# memoryboard31.net
KiCad netlist of a schematic drawn in EAGLE
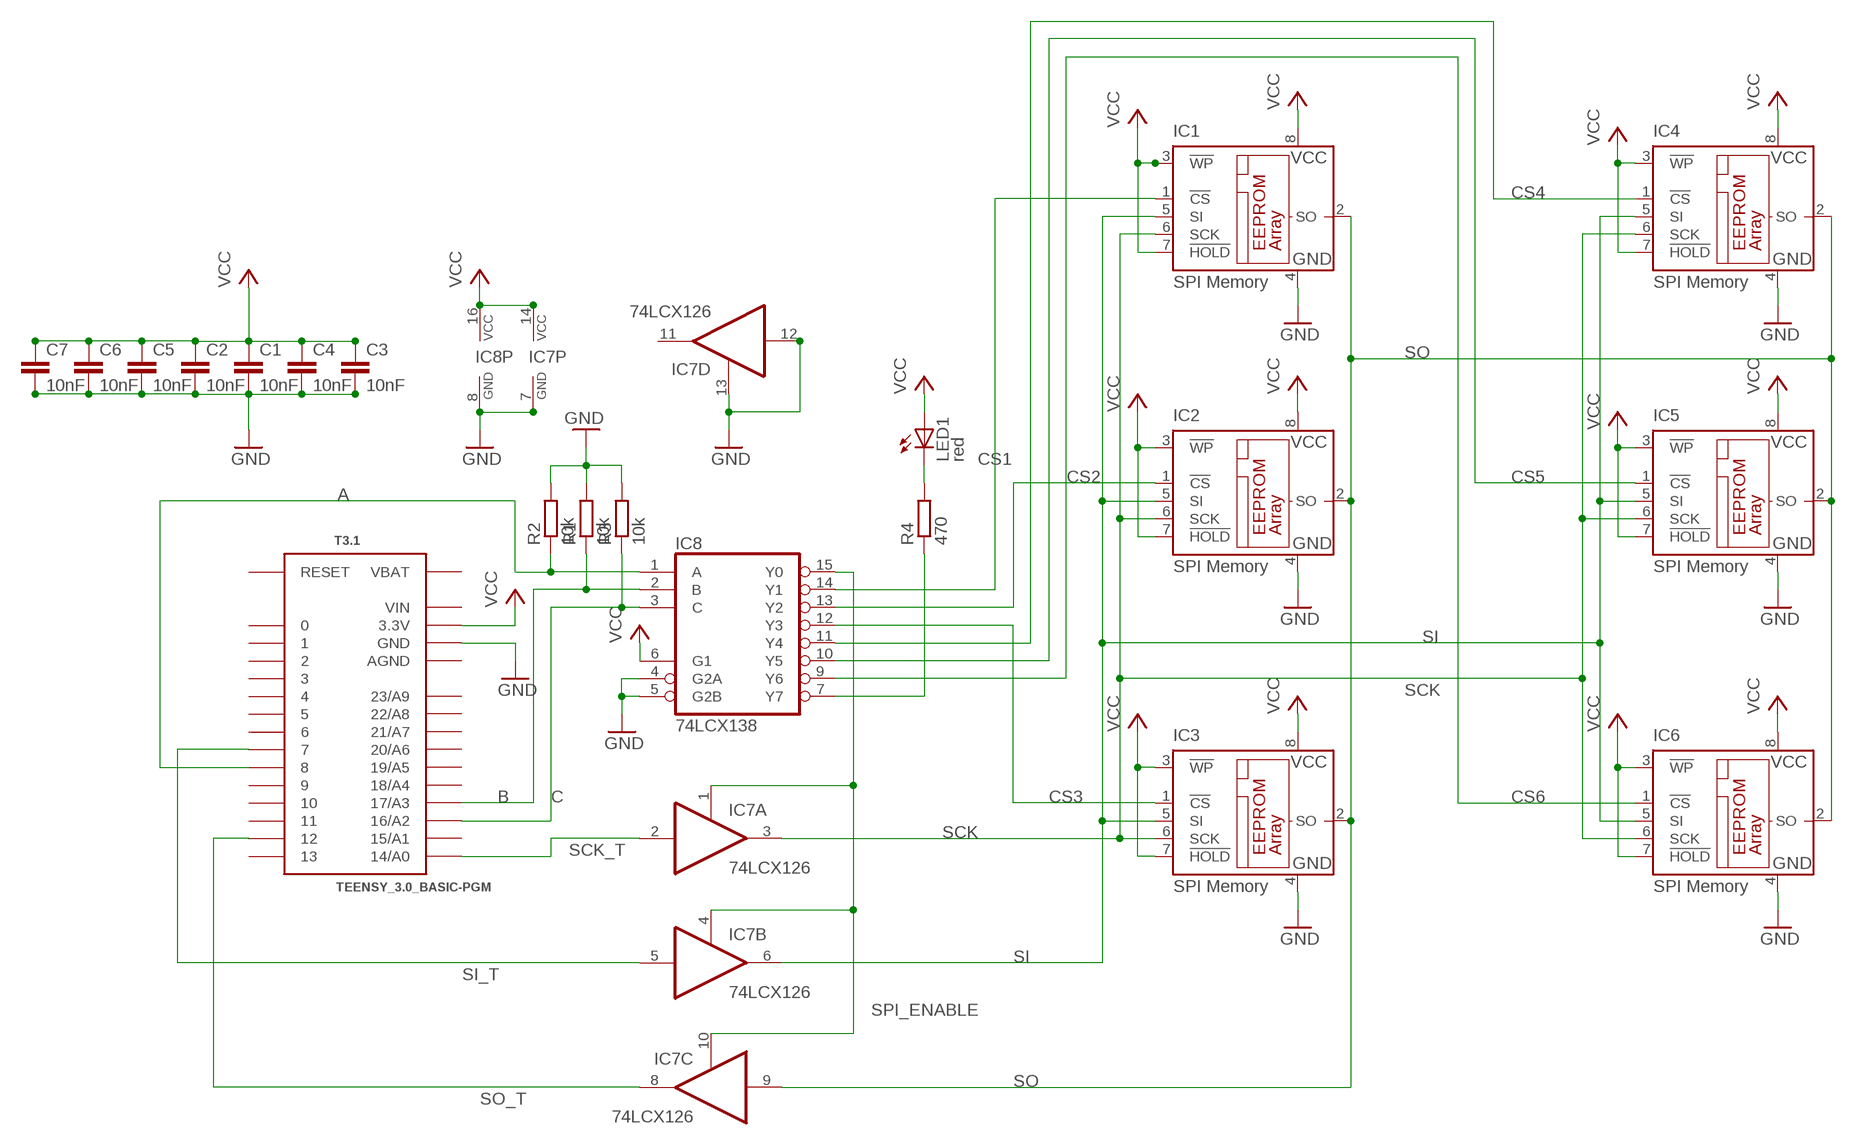
[diagram p0: schematic, sheet 1]

(export (version "E")
  (design (tool "Eeschema 10.0.6"))
  (components
    (comp (ref "C1")
      (value "10nF")
      (footprint "eagle-import:C0603")
      (libsource (lib "eagle-import") (part "C-EUC0603"))
    )
    (comp (ref "C2")
      (value "10nF")
      (footprint "eagle-import:C0603")
      (libsource (lib "eagle-import") (part "C-EUC0603"))
    )
    (comp (ref "C3")
      (value "10nF")
      (footprint "eagle-import:C0603")
      (libsource (lib "eagle-import") (part "C-EUC0603"))
    )
    (comp (ref "C4")
      (value "10nF")
      (footprint "eagle-import:C0603")
      (libsource (lib "eagle-import") (part "C-EUC0603"))
    )
    (comp (ref "C5")
      (value "10nF")
      (footprint "eagle-import:C0603")
      (libsource (lib "eagle-import") (part "C-EUC0603"))
    )
    (comp (ref "C6")
      (value "10nF")
      (footprint "eagle-import:C0603")
      (libsource (lib "eagle-import") (part "C-EUC0603"))
    )
    (comp (ref "C7")
      (value "10nF")
      (footprint "eagle-import:C0603")
      (libsource (lib "eagle-import") (part "C-EUC0603"))
    )
    (comp (ref "IC1")
      (value "SPI Memory")
      (footprint "eagle-import:SO-08")
      (fields (field (name "MF") "MICROCHIP") (field (name "MPN") "25C080/SN"))
      (libsource (lib "eagle-import") (part "25SNC080"))
    )
    (comp (ref "IC2")
      (value "SPI Memory")
      (footprint "eagle-import:SO-08")
      (fields (field (name "MF") "MICROCHIP") (field (name "MPN") "25C080/SN"))
      (libsource (lib "eagle-import") (part "25SNC080"))
    )
    (comp (ref "IC3")
      (value "SPI Memory")
      (footprint "eagle-import:SO-08")
      (fields (field (name "MF") "MICROCHIP") (field (name "MPN") "25C080/SN"))
      (libsource (lib "eagle-import") (part "25SNC080"))
    )
    (comp (ref "IC4")
      (value "SPI Memory")
      (footprint "eagle-import:SO-08")
      (fields (field (name "MF") "MICROCHIP") (field (name "MPN") "25C080/SN"))
      (libsource (lib "eagle-import") (part "25SNC080"))
    )
    (comp (ref "IC5")
      (value "SPI Memory")
      (footprint "eagle-import:SO-08")
      (fields (field (name "MF") "MICROCHIP") (field (name "MPN") "25C080/SN"))
      (libsource (lib "eagle-import") (part "25SNC080"))
    )
    (comp (ref "IC6")
      (value "SPI Memory")
      (footprint "eagle-import:SO-08")
      (fields (field (name "MF") "MICROCHIP") (field (name "MPN") "25C080/SN"))
      (libsource (lib "eagle-import") (part "25SNC080"))
    )
    (comp (ref "IC7")
      (value "74LCX126")
      (footprint "eagle-import:SO14")
      (libsource (lib "eagle-import") (part "74126DAC"))
    )
    (comp (ref "IC8")
      (value "74LCX138")
      (footprint "eagle-import:SO16")
      (libsource (lib "eagle-import") (part "74138DHC"))
    )
    (comp (ref "LED1")
      (value "red")
      (footprint "eagle-import:SML0603")
      (libsource (lib "eagle-import") (part "LEDSML0603"))
    )
    (comp (ref "R1")
      (value "10k")
      (footprint "eagle-import:R0603")
      (libsource (lib "eagle-import") (part "R-EU_R0603"))
    )
    (comp (ref "R2")
      (value "10k")
      (footprint "eagle-import:R0603")
      (libsource (lib "eagle-import") (part "R-EU_R0603"))
    )
    (comp (ref "R3")
      (value "10k")
      (footprint "eagle-import:R0603")
      (libsource (lib "eagle-import") (part "R-EU_R0603"))
    )
    (comp (ref "R4")
      (value "470")
      (footprint "eagle-import:R0603")
      (libsource (lib "eagle-import") (part "R-EU_R0603"))
    )
    (comp (ref "T3.1")
      (value "TEENSY_3.0_BASIC-PGM")
      (footprint "eagle-import:TEENSY_3.0_BASIC-PGM")
      (libsource (lib "eagle-import") (part "TEENSY_3.0_BASIC-PGM"))
    )
  )
  (nets
    (net (code "1") (name "/A") (class "Default")
      (node (ref "IC8") (pin "1") (pinfunction "A_1") (pintype "input"))
      (node (ref "R2") (pin "1") (pinfunction "1_1") (pintype "passive"))
      (node (ref "T3.1") (pin "8") (pinfunction "8_8") (pintype "bidirectional"))
    )
    (net (code "2") (name "/AGND") (class "Default")
      (node (ref "T3.1") (pin "AGND") (pinfunction "AGND_AGND") (pintype "power_in"))
    )
    (net (code "3") (name "/B") (class "Default")
      (node (ref "IC8") (pin "2") (pinfunction "B_2") (pintype "input"))
      (node (ref "R1") (pin "1") (pinfunction "1_1") (pintype "passive"))
      (node (ref "T3.1") (pin "17/A3") (pinfunction "17/A3_17/A3") (pintype "bidirectional"))
    )
    (net (code "4") (name "/C") (class "Default")
      (node (ref "IC8") (pin "3") (pinfunction "C_3") (pintype "input"))
      (node (ref "R3") (pin "1") (pinfunction "1_1") (pintype "passive"))
      (node (ref "T3.1") (pin "16/A2") (pinfunction "16/A2_16/A2") (pintype "bidirectional"))
    )
    (net (code "5") (name "/CS1") (class "Default")
      (node (ref "IC1") (pin "1") (pinfunction "~{CS}_1") (pintype "input"))
      (node (ref "IC8") (pin "14") (pinfunction "Y1_14") (pintype "output"))
    )
    (net (code "6") (name "/CS2") (class "Default")
      (node (ref "IC2") (pin "1") (pinfunction "~{CS}_1") (pintype "input"))
      (node (ref "IC8") (pin "13") (pinfunction "Y2_13") (pintype "output"))
    )
    (net (code "7") (name "/CS3") (class "Default")
      (node (ref "IC3") (pin "1") (pinfunction "~{CS}_1") (pintype "input"))
      (node (ref "IC8") (pin "12") (pinfunction "Y3_12") (pintype "output"))
    )
    (net (code "8") (name "/CS4") (class "Default")
      (node (ref "IC4") (pin "1") (pinfunction "~{CS}_1") (pintype "input"))
      (node (ref "IC8") (pin "11") (pinfunction "Y4_11") (pintype "output"))
    )
    (net (code "9") (name "/CS5") (class "Default")
      (node (ref "IC5") (pin "1") (pinfunction "~{CS}_1") (pintype "input"))
      (node (ref "IC8") (pin "10") (pinfunction "Y5_10") (pintype "output"))
    )
    (net (code "10") (name "/CS6") (class "Default")
      (node (ref "IC6") (pin "1") (pinfunction "~{CS}_1") (pintype "input"))
      (node (ref "IC8") (pin "9") (pinfunction "Y6_9") (pintype "output"))
    )
    (net (code "11") (name "/SCK") (class "Default")
      (node (ref "IC1") (pin "6") (pinfunction "SCK_6") (pintype "input"))
      (node (ref "IC2") (pin "6") (pinfunction "SCK_6") (pintype "input"))
      (node (ref "IC3") (pin "6") (pinfunction "SCK_6") (pintype "input"))
      (node (ref "IC4") (pin "6") (pinfunction "SCK_6") (pintype "input"))
      (node (ref "IC5") (pin "6") (pinfunction "SCK_6") (pintype "input"))
      (node (ref "IC6") (pin "6") (pinfunction "SCK_6") (pintype "input"))
      (node (ref "IC7") (pin "3") (pinfunction "O_3") (pintype "output"))
    )
    (net (code "12") (name "/SCK_T") (class "Default")
      (node (ref "IC7") (pin "2") (pinfunction "I_2") (pintype "input"))
      (node (ref "T3.1") (pin "14/A0") (pinfunction "14/A0_14/A0") (pintype "bidirectional"))
    )
    (net (code "13") (name "/SI") (class "Default")
      (node (ref "IC1") (pin "5") (pinfunction "SI_5") (pintype "input"))
      (node (ref "IC2") (pin "5") (pinfunction "SI_5") (pintype "input"))
      (node (ref "IC3") (pin "5") (pinfunction "SI_5") (pintype "input"))
      (node (ref "IC4") (pin "5") (pinfunction "SI_5") (pintype "input"))
      (node (ref "IC5") (pin "5") (pinfunction "SI_5") (pintype "input"))
      (node (ref "IC6") (pin "5") (pinfunction "SI_5") (pintype "input"))
      (node (ref "IC7") (pin "6") (pinfunction "O_6") (pintype "output"))
    )
    (net (code "14") (name "/SI_T") (class "Default")
      (node (ref "IC7") (pin "5") (pinfunction "I_5") (pintype "input"))
      (node (ref "T3.1") (pin "7") (pinfunction "7_7") (pintype "bidirectional"))
    )
    (net (code "15") (name "/SO") (class "Default")
      (node (ref "IC1") (pin "2") (pinfunction "SO_2") (pintype "bidirectional"))
      (node (ref "IC2") (pin "2") (pinfunction "SO_2") (pintype "bidirectional"))
      (node (ref "IC3") (pin "2") (pinfunction "SO_2") (pintype "bidirectional"))
      (node (ref "IC4") (pin "2") (pinfunction "SO_2") (pintype "bidirectional"))
      (node (ref "IC5") (pin "2") (pinfunction "SO_2") (pintype "bidirectional"))
      (node (ref "IC6") (pin "2") (pinfunction "SO_2") (pintype "bidirectional"))
      (node (ref "IC7") (pin "9") (pinfunction "I_9") (pintype "input"))
    )
    (net (code "16") (name "/SO_T") (class "Default")
      (node (ref "IC7") (pin "8") (pinfunction "O_8") (pintype "output"))
      (node (ref "T3.1") (pin "12") (pinfunction "12_12") (pintype "bidirectional"))
    )
    (net (code "17") (name "/SPI_ENABLE") (class "Default")
      (node (ref "IC7") (pin "1") (pinfunction "OE_1") (pintype "input"))
      (node (ref "IC7") (pin "10") (pinfunction "OE_10") (pintype "input"))
      (node (ref "IC7") (pin "4") (pinfunction "OE_4") (pintype "input"))
      (node (ref "IC8") (pin "15") (pinfunction "Y0_15") (pintype "output"))
    )
    (net (code "18") (name "/VBAT") (class "Default")
      (node (ref "T3.1") (pin "VBAT") (pinfunction "VBAT_VBAT") (pintype "power_in"))
    )
    (net (code "19") (name "/VIN") (class "Default")
      (node (ref "T3.1") (pin "VIN") (pinfunction "VIN_VIN") (pintype "power_in"))
    )
    (net (code "20") (name "GND") (class "Default")
      (node (ref "C1") (pin "2") (pinfunction "2_2") (pintype "passive"))
      (node (ref "C2") (pin "2") (pinfunction "2_2") (pintype "passive"))
      (node (ref "C3") (pin "2") (pinfunction "2_2") (pintype "passive"))
      (node (ref "C4") (pin "2") (pinfunction "2_2") (pintype "passive"))
      (node (ref "C5") (pin "2") (pinfunction "2_2") (pintype "passive"))
      (node (ref "C6") (pin "2") (pinfunction "2_2") (pintype "passive"))
      (node (ref "C7") (pin "2") (pinfunction "2_2") (pintype "passive"))
      (node (ref "IC1") (pin "4") (pinfunction "GND_4") (pintype "power_in"))
      (node (ref "IC2") (pin "4") (pinfunction "GND_4") (pintype "power_in"))
      (node (ref "IC3") (pin "4") (pinfunction "GND_4") (pintype "power_in"))
      (node (ref "IC4") (pin "4") (pinfunction "GND_4") (pintype "power_in"))
      (node (ref "IC5") (pin "4") (pinfunction "GND_4") (pintype "power_in"))
      (node (ref "IC6") (pin "4") (pinfunction "GND_4") (pintype "power_in"))
      (node (ref "IC7") (pin "12") (pinfunction "I_12") (pintype "input"))
      (node (ref "IC7") (pin "13") (pinfunction "OE_13") (pintype "input"))
      (node (ref "IC7") (pin "7") (pinfunction "GND_7") (pintype "power_in"))
      (node (ref "IC8") (pin "4") (pinfunction "G2A_4") (pintype "input"))
      (node (ref "IC8") (pin "5") (pinfunction "G2B_5") (pintype "input"))
      (node (ref "IC8") (pin "8") (pinfunction "GND_8") (pintype "power_in"))
      (node (ref "R1") (pin "2") (pinfunction "2_2") (pintype "passive"))
      (node (ref "R2") (pin "2") (pinfunction "2_2") (pintype "passive"))
      (node (ref "R3") (pin "2") (pinfunction "2_2") (pintype "passive"))
      (node (ref "T3.1") (pin "GND") (pinfunction "GND_GND") (pintype "power_in"))
      (node (ref "T3.1") (pin "GND1") (pinfunction "GND_GND1") (pintype "power_in"))
    )
    (net (code "21") (name "Net-(IC8A-Y7)") (class "Default")
      (node (ref "IC8") (pin "7") (pinfunction "Y7_7") (pintype "output"))
      (node (ref "R4") (pin "1") (pinfunction "1_1") (pintype "passive"))
    )
    (net (code "22") (name "Net-(LED1-PadC)") (class "Default")
      (node (ref "LED1") (pin "C") (pinfunction "C_C") (pintype "passive"))
      (node (ref "R4") (pin "2") (pinfunction "2_2") (pintype "passive"))
    )
    (net (code "23") (name "VCC") (class "Default")
      (node (ref "C1") (pin "1") (pinfunction "1_1") (pintype "passive"))
      (node (ref "C2") (pin "1") (pinfunction "1_1") (pintype "passive"))
      (node (ref "C3") (pin "1") (pinfunction "1_1") (pintype "passive"))
      (node (ref "C4") (pin "1") (pinfunction "1_1") (pintype "passive"))
      (node (ref "C5") (pin "1") (pinfunction "1_1") (pintype "passive"))
      (node (ref "C6") (pin "1") (pinfunction "1_1") (pintype "passive"))
      (node (ref "C7") (pin "1") (pinfunction "1_1") (pintype "passive"))
      (node (ref "IC1") (pin "3") (pinfunction "~{WP}_3") (pintype "input"))
      (node (ref "IC1") (pin "7") (pinfunction "~{HOLD}_7") (pintype "input"))
      (node (ref "IC1") (pin "8") (pinfunction "VCC_8") (pintype "power_in"))
      (node (ref "IC2") (pin "3") (pinfunction "~{WP}_3") (pintype "input"))
      (node (ref "IC2") (pin "7") (pinfunction "~{HOLD}_7") (pintype "input"))
      (node (ref "IC2") (pin "8") (pinfunction "VCC_8") (pintype "power_in"))
      (node (ref "IC3") (pin "3") (pinfunction "~{WP}_3") (pintype "input"))
      (node (ref "IC3") (pin "7") (pinfunction "~{HOLD}_7") (pintype "input"))
      (node (ref "IC3") (pin "8") (pinfunction "VCC_8") (pintype "power_in"))
      (node (ref "IC4") (pin "3") (pinfunction "~{WP}_3") (pintype "input"))
      (node (ref "IC4") (pin "7") (pinfunction "~{HOLD}_7") (pintype "input"))
      (node (ref "IC4") (pin "8") (pinfunction "VCC_8") (pintype "power_in"))
      (node (ref "IC5") (pin "3") (pinfunction "~{WP}_3") (pintype "input"))
      (node (ref "IC5") (pin "7") (pinfunction "~{HOLD}_7") (pintype "input"))
      (node (ref "IC5") (pin "8") (pinfunction "VCC_8") (pintype "power_in"))
      (node (ref "IC6") (pin "3") (pinfunction "~{WP}_3") (pintype "input"))
      (node (ref "IC6") (pin "7") (pinfunction "~{HOLD}_7") (pintype "input"))
      (node (ref "IC6") (pin "8") (pinfunction "VCC_8") (pintype "power_in"))
      (node (ref "IC7") (pin "14") (pinfunction "VCC_14") (pintype "power_in"))
      (node (ref "IC8") (pin "16") (pinfunction "VCC_16") (pintype "power_in"))
      (node (ref "IC8") (pin "6") (pinfunction "G1_6") (pintype "input"))
      (node (ref "LED1") (pin "A") (pinfunction "A_A") (pintype "passive"))
      (node (ref "T3.1") (pin "3.3V") (pinfunction "3.3V_3.3V") (pintype "power_in"))
      (node (ref "T3.1") (pin "3.3V1") (pinfunction "3.3V_3.3V1") (pintype "power_in"))
    )
    (net (code "24") (name "unconnected-(IC7D-O-Pad11)") (class "Default")
      (node (ref "IC7") (pin "11") (pinfunction "O_11") (pintype "output"))
    )
    (net (code "25") (name "unconnected-(T3.1-Pad0)") (class "Default")
      (node (ref "T3.1") (pin "0") (pinfunction "0_0") (pintype "bidirectional"))
    )
    (net (code "26") (name "unconnected-(T3.1-Pad1)") (class "Default")
      (node (ref "T3.1") (pin "1") (pinfunction "1_1") (pintype "bidirectional"))
    )
    (net (code "27") (name "unconnected-(T3.1-Pad2)") (class "Default")
      (node (ref "T3.1") (pin "2") (pinfunction "2_2") (pintype "bidirectional"))
    )
    (net (code "28") (name "unconnected-(T3.1-Pad3)") (class "Default")
      (node (ref "T3.1") (pin "3") (pinfunction "3_3") (pintype "bidirectional"))
    )
    (net (code "29") (name "unconnected-(T3.1-Pad4)") (class "Default")
      (node (ref "T3.1") (pin "4") (pinfunction "4_4") (pintype "bidirectional"))
    )
    (net (code "30") (name "unconnected-(T3.1-Pad5)") (class "Default")
      (node (ref "T3.1") (pin "5") (pinfunction "5_5") (pintype "bidirectional"))
    )
    (net (code "31") (name "unconnected-(T3.1-Pad6)") (class "Default")
      (node (ref "T3.1") (pin "6") (pinfunction "6_6") (pintype "bidirectional"))
    )
    (net (code "32") (name "unconnected-(T3.1-Pad9)") (class "Default")
      (node (ref "T3.1") (pin "9") (pinfunction "9_9") (pintype "bidirectional"))
    )
    (net (code "33") (name "unconnected-(T3.1-Pad10)") (class "Default")
      (node (ref "T3.1") (pin "10") (pinfunction "10_10") (pintype "bidirectional"))
    )
    (net (code "34") (name "unconnected-(T3.1-Pad11)") (class "Default")
      (node (ref "T3.1") (pin "11") (pinfunction "11_11") (pintype "bidirectional"))
    )
    (net (code "35") (name "unconnected-(T3.1-Pad13)") (class "Default")
      (node (ref "T3.1") (pin "13") (pinfunction "13_13") (pintype "bidirectional"))
    )
    (net (code "36") (name "unconnected-(T3.1-Pad15{slash}A1)") (class "Default")
      (node (ref "T3.1") (pin "15/A1") (pinfunction "15/A1_15/A1") (pintype "bidirectional"))
    )
    (net (code "37") (name "unconnected-(T3.1-Pad18{slash}A4)") (class "Default")
      (node (ref "T3.1") (pin "18/A4") (pinfunction "18/A4_18/A4") (pintype "bidirectional"))
    )
    (net (code "38") (name "unconnected-(T3.1-Pad19{slash}A5)") (class "Default")
      (node (ref "T3.1") (pin "19/A5") (pinfunction "19/A5_19/A5") (pintype "bidirectional"))
    )
    (net (code "39") (name "unconnected-(T3.1-Pad20{slash}A6)") (class "Default")
      (node (ref "T3.1") (pin "20/A6") (pinfunction "20/A6_20/A6") (pintype "bidirectional"))
    )
    (net (code "40") (name "unconnected-(T3.1-Pad21{slash}A7)") (class "Default")
      (node (ref "T3.1") (pin "21/A7") (pinfunction "21/A7_21/A7") (pintype "bidirectional"))
    )
    (net (code "41") (name "unconnected-(T3.1-Pad22{slash}A8)") (class "Default")
      (node (ref "T3.1") (pin "22/A8") (pinfunction "22/A8_22/A8") (pintype "bidirectional"))
    )
    (net (code "42") (name "unconnected-(T3.1-Pad23{slash}A9)") (class "Default")
      (node (ref "T3.1") (pin "23/A9") (pinfunction "23/A9_23/A9") (pintype "bidirectional"))
    )
    (net (code "43") (name "unconnected-(T3.1-PadRESET)") (class "Default")
      (node (ref "T3.1") (pin "RESET") (pinfunction "RESET_RESET") (pintype "bidirectional"))
    )
  )
)
